# Quad_VCA_no_pots_CTRL_v1.net
KiCad netlist of a schematic drawn in EAGLE
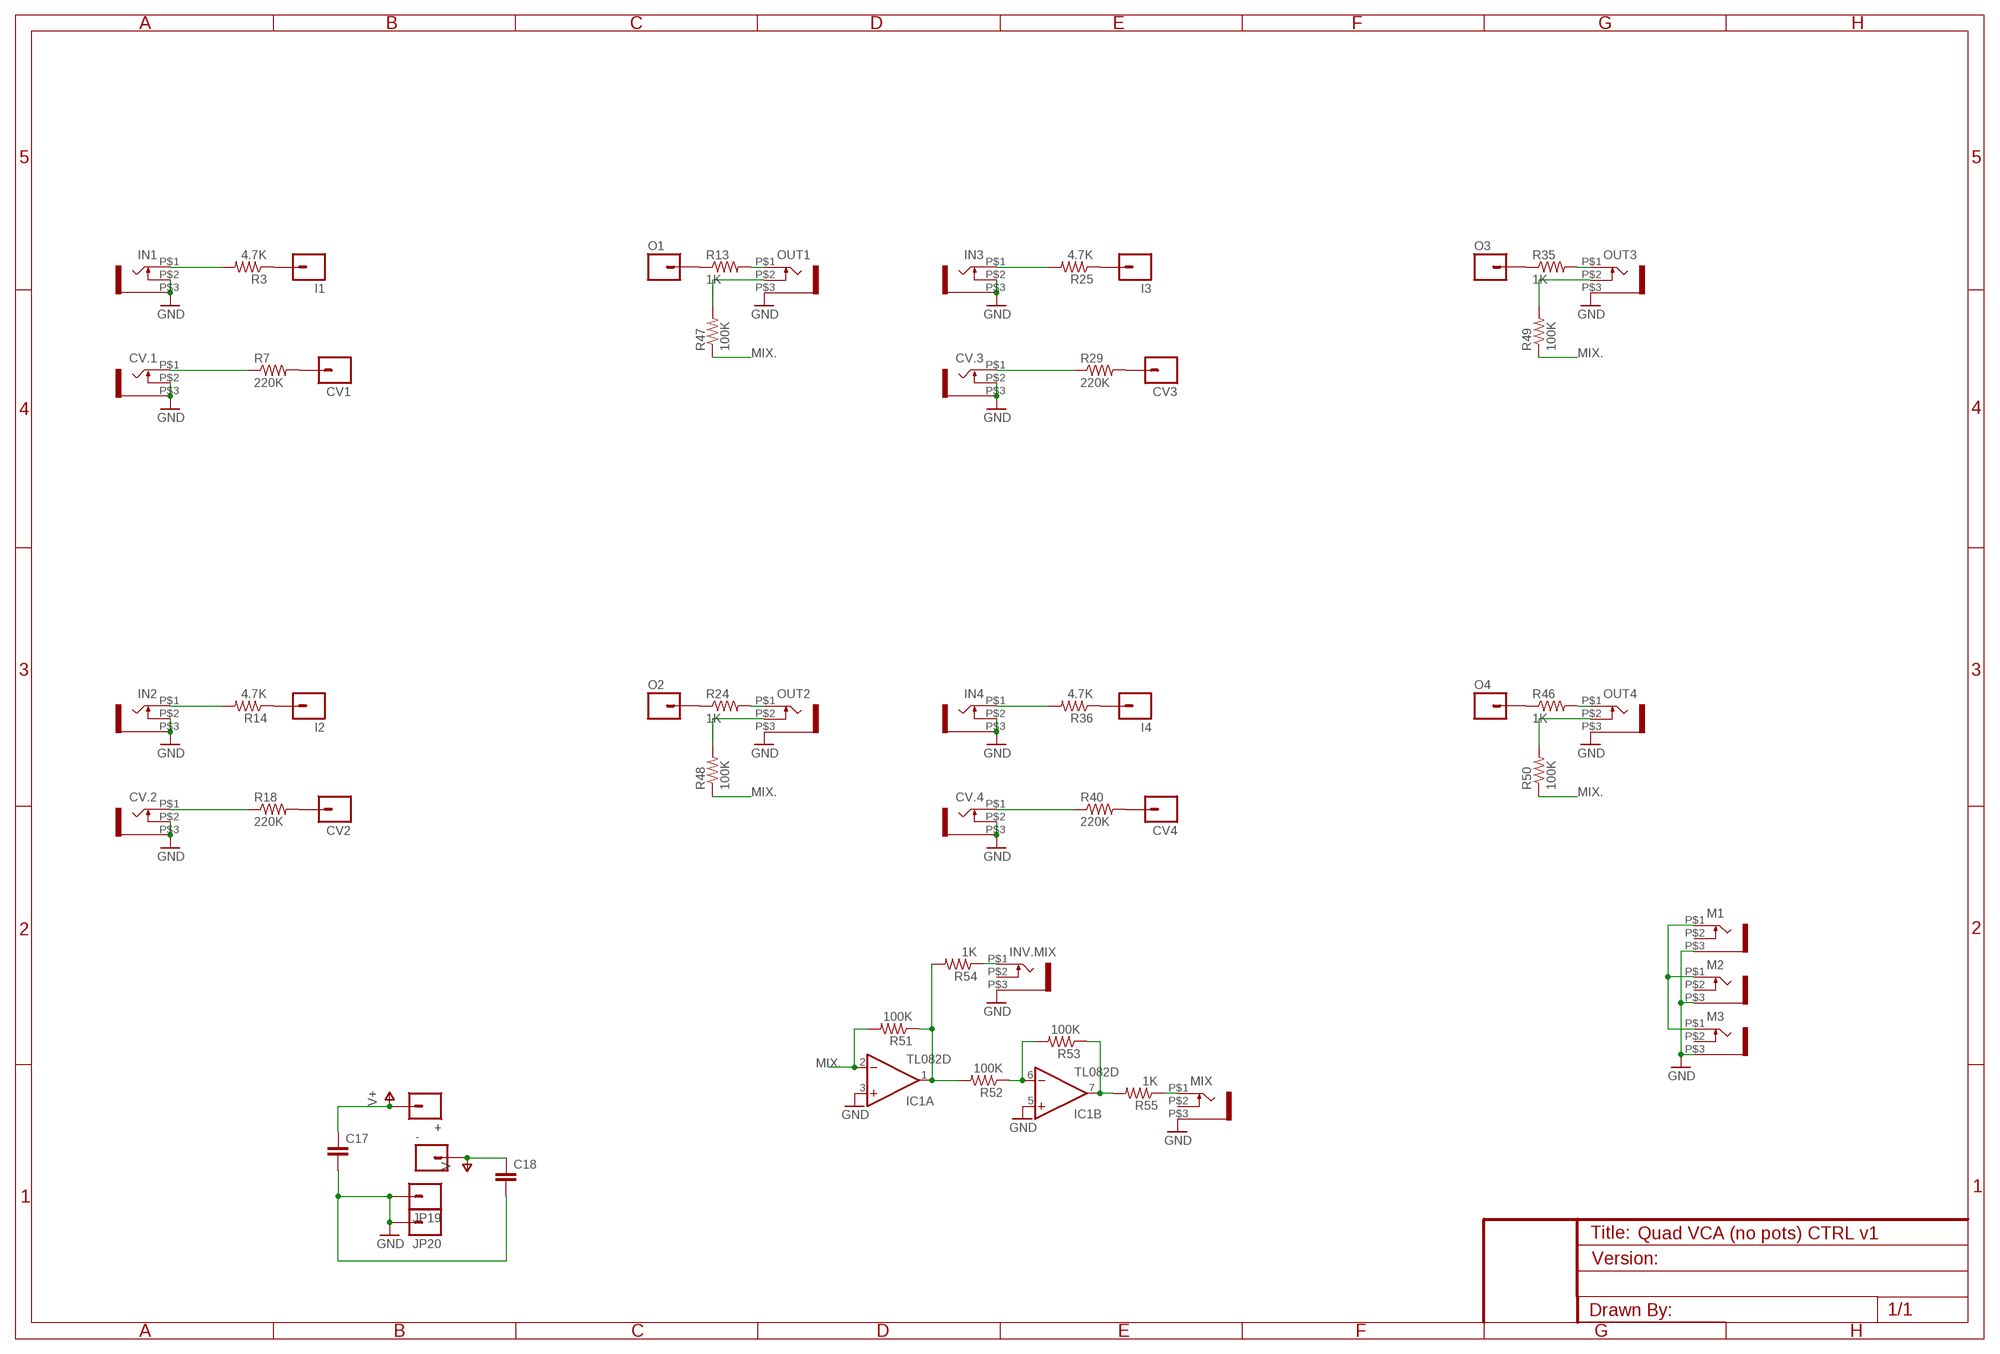
[diagram p0: schematic, sheet 1]

(export (version "E")
  (design (tool "Eeschema 10.0.6"))
  (components
    (comp (ref "+")
      (value "M01PTH")
      (footprint "eagle-import:1X01")
      (libsource (lib "eagle-import") (part "M01PTH"))
    )
    (comp (ref "-")
      (value "M01PTH")
      (footprint "eagle-import:1X01")
      (libsource (lib "eagle-import") (part "M01PTH"))
    )
    (comp (ref "C17")
      (value "CAP0805")
      (footprint "eagle-import:0805")
      (libsource (lib "eagle-import") (part "CAP0805"))
    )
    (comp (ref "C18")
      (value "CAP0805")
      (footprint "eagle-import:0805")
      (libsource (lib "eagle-import") (part "CAP0805"))
    )
    (comp (ref "CV.1")
      (value "WQP-PJ301M-12_JACK")
      (footprint "eagle-import:WQP-PJ301M-12_JACK")
      (libsource (lib "eagle-import") (part "WQP-PJ301M-12_JACK"))
    )
    (comp (ref "CV.2")
      (value "WQP-PJ301M-12_JACK")
      (footprint "eagle-import:WQP-PJ301M-12_JACK")
      (libsource (lib "eagle-import") (part "WQP-PJ301M-12_JACK"))
    )
    (comp (ref "CV.3")
      (value "WQP-PJ301M-12_JACK")
      (footprint "eagle-import:WQP-PJ301M-12_JACK")
      (libsource (lib "eagle-import") (part "WQP-PJ301M-12_JACK"))
    )
    (comp (ref "CV.4")
      (value "WQP-PJ301M-12_JACK")
      (footprint "eagle-import:WQP-PJ301M-12_JACK")
      (libsource (lib "eagle-import") (part "WQP-PJ301M-12_JACK"))
    )
    (comp (ref "CV1")
      (value "M01PTH")
      (footprint "eagle-import:1X01")
      (libsource (lib "eagle-import") (part "M01PTH"))
    )
    (comp (ref "CV2")
      (value "M01PTH")
      (footprint "eagle-import:1X01")
      (libsource (lib "eagle-import") (part "M01PTH"))
    )
    (comp (ref "CV3")
      (value "M01PTH")
      (footprint "eagle-import:1X01")
      (libsource (lib "eagle-import") (part "M01PTH"))
    )
    (comp (ref "CV4")
      (value "M01PTH")
      (footprint "eagle-import:1X01")
      (libsource (lib "eagle-import") (part "M01PTH"))
    )
    (comp (ref "I1")
      (value "M01PTH")
      (footprint "eagle-import:1X01")
      (libsource (lib "eagle-import") (part "M01PTH"))
    )
    (comp (ref "I2")
      (value "M01PTH")
      (footprint "eagle-import:1X01")
      (libsource (lib "eagle-import") (part "M01PTH"))
    )
    (comp (ref "I3")
      (value "M01PTH")
      (footprint "eagle-import:1X01")
      (libsource (lib "eagle-import") (part "M01PTH"))
    )
    (comp (ref "I4")
      (value "M01PTH")
      (footprint "eagle-import:1X01")
      (libsource (lib "eagle-import") (part "M01PTH"))
    )
    (comp (ref "IC1")
      (value "TL082D")
      (footprint "eagle-import:SO08")
      (libsource (lib "eagle-import") (part "TL082D"))
    )
    (comp (ref "IN1")
      (value "WQP-PJ301M-12_JACK")
      (footprint "eagle-import:WQP-PJ301M-12_JACK")
      (libsource (lib "eagle-import") (part "WQP-PJ301M-12_JACK"))
    )
    (comp (ref "IN2")
      (value "WQP-PJ301M-12_JACK")
      (footprint "eagle-import:WQP-PJ301M-12_JACK")
      (libsource (lib "eagle-import") (part "WQP-PJ301M-12_JACK"))
    )
    (comp (ref "IN3")
      (value "WQP-PJ301M-12_JACK")
      (footprint "eagle-import:WQP-PJ301M-12_JACK")
      (libsource (lib "eagle-import") (part "WQP-PJ301M-12_JACK"))
    )
    (comp (ref "IN4")
      (value "WQP-PJ301M-12_JACK")
      (footprint "eagle-import:WQP-PJ301M-12_JACK")
      (libsource (lib "eagle-import") (part "WQP-PJ301M-12_JACK"))
    )
    (comp (ref "INV.MIX")
      (value "WQP-PJ301M-12_JACK")
      (footprint "eagle-import:WQP-PJ301M-12_JACK")
      (libsource (lib "eagle-import") (part "WQP-PJ301M-12_JACK"))
    )
    (comp (ref "JP19")
      (value "M01PTH")
      (footprint "eagle-import:1X01")
      (libsource (lib "eagle-import") (part "M01PTH"))
    )
    (comp (ref "JP20")
      (value "M01PTH")
      (footprint "eagle-import:1X01")
      (libsource (lib "eagle-import") (part "M01PTH"))
    )
    (comp (ref "M1")
      (value "WQP-PJ301M-12_JACK")
      (footprint "eagle-import:WQP-PJ301M-12_JACK")
      (libsource (lib "eagle-import") (part "WQP-PJ301M-12_JACK"))
    )
    (comp (ref "M2")
      (value "WQP-PJ301M-12_JACK")
      (footprint "eagle-import:WQP-PJ301M-12_JACK")
      (libsource (lib "eagle-import") (part "WQP-PJ301M-12_JACK"))
    )
    (comp (ref "M3")
      (value "WQP-PJ301M-12_JACK")
      (footprint "eagle-import:WQP-PJ301M-12_JACK")
      (libsource (lib "eagle-import") (part "WQP-PJ301M-12_JACK"))
    )
    (comp (ref "MIX")
      (value "WQP-PJ301M-12_JACK")
      (footprint "eagle-import:WQP-PJ301M-12_JACK")
      (libsource (lib "eagle-import") (part "WQP-PJ301M-12_JACK"))
    )
    (comp (ref "O1")
      (value "M01PTH")
      (footprint "eagle-import:1X01")
      (libsource (lib "eagle-import") (part "M01PTH"))
    )
    (comp (ref "O2")
      (value "M01PTH")
      (footprint "eagle-import:1X01")
      (libsource (lib "eagle-import") (part "M01PTH"))
    )
    (comp (ref "O3")
      (value "M01PTH")
      (footprint "eagle-import:1X01")
      (libsource (lib "eagle-import") (part "M01PTH"))
    )
    (comp (ref "O4")
      (value "M01PTH")
      (footprint "eagle-import:1X01")
      (libsource (lib "eagle-import") (part "M01PTH"))
    )
    (comp (ref "OUT1")
      (value "WQP-PJ301M-12_JACK")
      (footprint "eagle-import:WQP-PJ301M-12_JACK")
      (libsource (lib "eagle-import") (part "WQP-PJ301M-12_JACK"))
    )
    (comp (ref "OUT2")
      (value "WQP-PJ301M-12_JACK")
      (footprint "eagle-import:WQP-PJ301M-12_JACK")
      (libsource (lib "eagle-import") (part "WQP-PJ301M-12_JACK"))
    )
    (comp (ref "OUT3")
      (value "WQP-PJ301M-12_JACK")
      (footprint "eagle-import:WQP-PJ301M-12_JACK")
      (libsource (lib "eagle-import") (part "WQP-PJ301M-12_JACK"))
    )
    (comp (ref "OUT4")
      (value "WQP-PJ301M-12_JACK")
      (footprint "eagle-import:WQP-PJ301M-12_JACK")
      (libsource (lib "eagle-import") (part "WQP-PJ301M-12_JACK"))
    )
    (comp (ref "R3")
      (value "4.7K")
      (footprint "eagle-import:0805")
      (libsource (lib "eagle-import") (part "RESISTOR0805-RES"))
    )
    (comp (ref "R7")
      (value "220K")
      (footprint "eagle-import:0805")
      (libsource (lib "eagle-import") (part "RESISTOR0805-RES"))
    )
    (comp (ref "R13")
      (value "1K")
      (footprint "eagle-import:0805")
      (libsource (lib "eagle-import") (part "RESISTOR0805-RES"))
    )
    (comp (ref "R14")
      (value "4.7K")
      (footprint "eagle-import:0805")
      (libsource (lib "eagle-import") (part "RESISTOR0805-RES"))
    )
    (comp (ref "R18")
      (value "220K")
      (footprint "eagle-import:0805")
      (libsource (lib "eagle-import") (part "RESISTOR0805-RES"))
    )
    (comp (ref "R24")
      (value "1K")
      (footprint "eagle-import:0805")
      (libsource (lib "eagle-import") (part "RESISTOR0805-RES"))
    )
    (comp (ref "R25")
      (value "4.7K")
      (footprint "eagle-import:0805")
      (libsource (lib "eagle-import") (part "RESISTOR0805-RES"))
    )
    (comp (ref "R29")
      (value "220K")
      (footprint "eagle-import:0805")
      (libsource (lib "eagle-import") (part "RESISTOR0805-RES"))
    )
    (comp (ref "R35")
      (value "1K")
      (footprint "eagle-import:0805")
      (libsource (lib "eagle-import") (part "RESISTOR0805-RES"))
    )
    (comp (ref "R36")
      (value "4.7K")
      (footprint "eagle-import:0805")
      (libsource (lib "eagle-import") (part "RESISTOR0805-RES"))
    )
    (comp (ref "R40")
      (value "220K")
      (footprint "eagle-import:0805")
      (libsource (lib "eagle-import") (part "RESISTOR0805-RES"))
    )
    (comp (ref "R46")
      (value "1K")
      (footprint "eagle-import:0805")
      (libsource (lib "eagle-import") (part "RESISTOR0805-RES"))
    )
    (comp (ref "R47")
      (value "100K")
      (footprint "eagle-import:0805")
      (libsource (lib "eagle-import") (part "RESISTOR0805-RES"))
    )
    (comp (ref "R48")
      (value "100K")
      (footprint "eagle-import:0805")
      (libsource (lib "eagle-import") (part "RESISTOR0805-RES"))
    )
    (comp (ref "R49")
      (value "100K")
      (footprint "eagle-import:0805")
      (libsource (lib "eagle-import") (part "RESISTOR0805-RES"))
    )
    (comp (ref "R50")
      (value "100K")
      (footprint "eagle-import:0805")
      (libsource (lib "eagle-import") (part "RESISTOR0805-RES"))
    )
    (comp (ref "R51")
      (value "100K")
      (footprint "eagle-import:0805")
      (libsource (lib "eagle-import") (part "RESISTOR0805-RES"))
    )
    (comp (ref "R52")
      (value "100K")
      (footprint "eagle-import:0805")
      (libsource (lib "eagle-import") (part "RESISTOR0805-RES"))
    )
    (comp (ref "R53")
      (value "100K")
      (footprint "eagle-import:0805")
      (libsource (lib "eagle-import") (part "RESISTOR0805-RES"))
    )
    (comp (ref "R54")
      (value "1K")
      (footprint "eagle-import:0805")
      (libsource (lib "eagle-import") (part "RESISTOR0805-RES"))
    )
    (comp (ref "R55")
      (value "1K")
      (footprint "eagle-import:0805")
      (libsource (lib "eagle-import") (part "RESISTOR0805-RES"))
    )
  )
  (nets
    (net (code "1") (name "/MIX.") (class "Default")
      (node (ref "IC1") (pin "2") (pinfunction "-IN_2") (pintype "input"))
      (node (ref "R47") (pin "1") (pinfunction "1_1") (pintype "passive"))
      (node (ref "R48") (pin "1") (pinfunction "1_1") (pintype "passive"))
      (node (ref "R49") (pin "1") (pinfunction "1_1") (pintype "passive"))
      (node (ref "R50") (pin "1") (pinfunction "1_1") (pintype "passive"))
      (node (ref "R51") (pin "2") (pinfunction "2_2") (pintype "passive"))
    )
    (net (code "2") (name "GND") (class "Default")
      (node (ref "C17") (pin "2") (pinfunction "2_2") (pintype "passive"))
      (node (ref "C18") (pin "2") (pinfunction "2_2") (pintype "passive"))
      (node (ref "CV.1") (pin "P$2") (pinfunction "3_P$2") (pintype "passive"))
      (node (ref "CV.1") (pin "P$3") (pinfunction "1_P$3") (pintype "passive"))
      (node (ref "CV.2") (pin "P$2") (pinfunction "3_P$2") (pintype "passive"))
      (node (ref "CV.2") (pin "P$3") (pinfunction "1_P$3") (pintype "passive"))
      (node (ref "CV.3") (pin "P$2") (pinfunction "3_P$2") (pintype "passive"))
      (node (ref "CV.3") (pin "P$3") (pinfunction "1_P$3") (pintype "passive"))
      (node (ref "CV.4") (pin "P$2") (pinfunction "3_P$2") (pintype "passive"))
      (node (ref "CV.4") (pin "P$3") (pinfunction "1_P$3") (pintype "passive"))
      (node (ref "IC1") (pin "3") (pinfunction "+IN_3") (pintype "input"))
      (node (ref "IC1") (pin "5") (pinfunction "+IN_5") (pintype "input"))
      (node (ref "IN1") (pin "P$2") (pinfunction "3_P$2") (pintype "passive"))
      (node (ref "IN1") (pin "P$3") (pinfunction "1_P$3") (pintype "passive"))
      (node (ref "IN2") (pin "P$2") (pinfunction "3_P$2") (pintype "passive"))
      (node (ref "IN2") (pin "P$3") (pinfunction "1_P$3") (pintype "passive"))
      (node (ref "IN3") (pin "P$2") (pinfunction "3_P$2") (pintype "passive"))
      (node (ref "IN3") (pin "P$3") (pinfunction "1_P$3") (pintype "passive"))
      (node (ref "IN4") (pin "P$2") (pinfunction "3_P$2") (pintype "passive"))
      (node (ref "IN4") (pin "P$3") (pinfunction "1_P$3") (pintype "passive"))
      (node (ref "INV.MIX") (pin "P$3") (pinfunction "1_P$3") (pintype "passive"))
      (node (ref "JP19") (pin "1") (pinfunction "1_1") (pintype "passive"))
      (node (ref "JP20") (pin "1") (pinfunction "1_1") (pintype "passive"))
      (node (ref "M1") (pin "P$3") (pinfunction "1_P$3") (pintype "passive"))
      (node (ref "M2") (pin "P$3") (pinfunction "1_P$3") (pintype "passive"))
      (node (ref "M3") (pin "P$3") (pinfunction "1_P$3") (pintype "passive"))
      (node (ref "MIX") (pin "P$3") (pinfunction "1_P$3") (pintype "passive"))
      (node (ref "OUT1") (pin "P$3") (pinfunction "1_P$3") (pintype "passive"))
      (node (ref "OUT2") (pin "P$3") (pinfunction "1_P$3") (pintype "passive"))
      (node (ref "OUT3") (pin "P$3") (pinfunction "1_P$3") (pintype "passive"))
      (node (ref "OUT4") (pin "P$3") (pinfunction "1_P$3") (pintype "passive"))
    )
    (net (code "3") (name "Net-(CV.1-2)") (class "Default")
      (node (ref "CV.1") (pin "P$1") (pinfunction "2_P$1") (pintype "passive"))
      (node (ref "R7") (pin "1") (pinfunction "1_1") (pintype "passive"))
    )
    (net (code "4") (name "Net-(CV.2-2)") (class "Default")
      (node (ref "CV.2") (pin "P$1") (pinfunction "2_P$1") (pintype "passive"))
      (node (ref "R18") (pin "1") (pinfunction "1_1") (pintype "passive"))
    )
    (net (code "5") (name "Net-(CV.3-2)") (class "Default")
      (node (ref "CV.3") (pin "P$1") (pinfunction "2_P$1") (pintype "passive"))
      (node (ref "R29") (pin "1") (pinfunction "1_1") (pintype "passive"))
    )
    (net (code "6") (name "Net-(CV.4-2)") (class "Default")
      (node (ref "CV.4") (pin "P$1") (pinfunction "2_P$1") (pintype "passive"))
      (node (ref "R40") (pin "1") (pinfunction "1_1") (pintype "passive"))
    )
    (net (code "7") (name "Net-(CV1-Pad1)") (class "Default")
      (node (ref "CV1") (pin "1") (pinfunction "1_1") (pintype "passive"))
      (node (ref "R7") (pin "2") (pinfunction "2_2") (pintype "passive"))
    )
    (net (code "8") (name "Net-(CV2-Pad1)") (class "Default")
      (node (ref "CV2") (pin "1") (pinfunction "1_1") (pintype "passive"))
      (node (ref "R18") (pin "2") (pinfunction "2_2") (pintype "passive"))
    )
    (net (code "9") (name "Net-(CV3-Pad1)") (class "Default")
      (node (ref "CV3") (pin "1") (pinfunction "1_1") (pintype "passive"))
      (node (ref "R29") (pin "2") (pinfunction "2_2") (pintype "passive"))
    )
    (net (code "10") (name "Net-(CV4-Pad1)") (class "Default")
      (node (ref "CV4") (pin "1") (pinfunction "1_1") (pintype "passive"))
      (node (ref "R40") (pin "2") (pinfunction "2_2") (pintype "passive"))
    )
    (net (code "11") (name "Net-(I1-Pad1)") (class "Default")
      (node (ref "I1") (pin "1") (pinfunction "1_1") (pintype "passive"))
      (node (ref "R3") (pin "1") (pinfunction "1_1") (pintype "passive"))
    )
    (net (code "12") (name "Net-(I2-Pad1)") (class "Default")
      (node (ref "I2") (pin "1") (pinfunction "1_1") (pintype "passive"))
      (node (ref "R14") (pin "1") (pinfunction "1_1") (pintype "passive"))
    )
    (net (code "13") (name "Net-(I3-Pad1)") (class "Default")
      (node (ref "I3") (pin "1") (pinfunction "1_1") (pintype "passive"))
      (node (ref "R25") (pin "1") (pinfunction "1_1") (pintype "passive"))
    )
    (net (code "14") (name "Net-(I4-Pad1)") (class "Default")
      (node (ref "I4") (pin "1") (pinfunction "1_1") (pintype "passive"))
      (node (ref "R36") (pin "1") (pinfunction "1_1") (pintype "passive"))
    )
    (net (code "15") (name "Net-(IC1A-OUT)") (class "Default")
      (node (ref "IC1") (pin "1") (pinfunction "OUT_1") (pintype "output"))
      (node (ref "R51") (pin "1") (pinfunction "1_1") (pintype "passive"))
      (node (ref "R52") (pin "2") (pinfunction "2_2") (pintype "passive"))
      (node (ref "R54") (pin "2") (pinfunction "2_2") (pintype "passive"))
    )
    (net (code "16") (name "Net-(IC1B--IN)") (class "Default")
      (node (ref "IC1") (pin "6") (pinfunction "-IN_6") (pintype "input"))
      (node (ref "R52") (pin "1") (pinfunction "1_1") (pintype "passive"))
      (node (ref "R53") (pin "2") (pinfunction "2_2") (pintype "passive"))
    )
    (net (code "17") (name "Net-(IC1B-OUT)") (class "Default")
      (node (ref "IC1") (pin "7") (pinfunction "OUT_7") (pintype "output"))
      (node (ref "R53") (pin "1") (pinfunction "1_1") (pintype "passive"))
      (node (ref "R55") (pin "2") (pinfunction "2_2") (pintype "passive"))
    )
    (net (code "18") (name "Net-(IN1-2)") (class "Default")
      (node (ref "IN1") (pin "P$1") (pinfunction "2_P$1") (pintype "passive"))
      (node (ref "R3") (pin "2") (pinfunction "2_2") (pintype "passive"))
    )
    (net (code "19") (name "Net-(IN2-2)") (class "Default")
      (node (ref "IN2") (pin "P$1") (pinfunction "2_P$1") (pintype "passive"))
      (node (ref "R14") (pin "2") (pinfunction "2_2") (pintype "passive"))
    )
    (net (code "20") (name "Net-(IN3-2)") (class "Default")
      (node (ref "IN3") (pin "P$1") (pinfunction "2_P$1") (pintype "passive"))
      (node (ref "R25") (pin "2") (pinfunction "2_2") (pintype "passive"))
    )
    (net (code "21") (name "Net-(IN4-2)") (class "Default")
      (node (ref "IN4") (pin "P$1") (pinfunction "2_P$1") (pintype "passive"))
      (node (ref "R36") (pin "2") (pinfunction "2_2") (pintype "passive"))
    )
    (net (code "22") (name "Net-(INV.MIX-2)") (class "Default")
      (node (ref "INV.MIX") (pin "P$1") (pinfunction "2_P$1") (pintype "passive"))
      (node (ref "R54") (pin "1") (pinfunction "1_1") (pintype "passive"))
    )
    (net (code "23") (name "Net-(M1-2)") (class "Default")
      (node (ref "M1") (pin "P$1") (pinfunction "2_P$1") (pintype "passive"))
      (node (ref "M2") (pin "P$1") (pinfunction "2_P$1") (pintype "passive"))
      (node (ref "M3") (pin "P$1") (pinfunction "2_P$1") (pintype "passive"))
    )
    (net (code "24") (name "Net-(MIX-2)") (class "Default")
      (node (ref "MIX") (pin "P$1") (pinfunction "2_P$1") (pintype "passive"))
      (node (ref "R55") (pin "1") (pinfunction "1_1") (pintype "passive"))
    )
    (net (code "25") (name "Net-(O1-Pad1)") (class "Default")
      (node (ref "O1") (pin "1") (pinfunction "1_1") (pintype "passive"))
      (node (ref "R13") (pin "1") (pinfunction "1_1") (pintype "passive"))
    )
    (net (code "26") (name "Net-(O2-Pad1)") (class "Default")
      (node (ref "O2") (pin "1") (pinfunction "1_1") (pintype "passive"))
      (node (ref "R24") (pin "1") (pinfunction "1_1") (pintype "passive"))
    )
    (net (code "27") (name "Net-(O3-Pad1)") (class "Default")
      (node (ref "O3") (pin "1") (pinfunction "1_1") (pintype "passive"))
      (node (ref "R35") (pin "1") (pinfunction "1_1") (pintype "passive"))
    )
    (net (code "28") (name "Net-(O4-Pad1)") (class "Default")
      (node (ref "O4") (pin "1") (pinfunction "1_1") (pintype "passive"))
      (node (ref "R46") (pin "1") (pinfunction "1_1") (pintype "passive"))
    )
    (net (code "29") (name "Net-(OUT1-2)") (class "Default")
      (node (ref "OUT1") (pin "P$1") (pinfunction "2_P$1") (pintype "passive"))
      (node (ref "R13") (pin "2") (pinfunction "2_2") (pintype "passive"))
    )
    (net (code "30") (name "Net-(OUT1-3)") (class "Default")
      (node (ref "OUT1") (pin "P$2") (pinfunction "3_P$2") (pintype "passive"))
      (node (ref "R47") (pin "2") (pinfunction "2_2") (pintype "passive"))
    )
    (net (code "31") (name "Net-(OUT2-2)") (class "Default")
      (node (ref "OUT2") (pin "P$1") (pinfunction "2_P$1") (pintype "passive"))
      (node (ref "R24") (pin "2") (pinfunction "2_2") (pintype "passive"))
    )
    (net (code "32") (name "Net-(OUT2-3)") (class "Default")
      (node (ref "OUT2") (pin "P$2") (pinfunction "3_P$2") (pintype "passive"))
      (node (ref "R48") (pin "2") (pinfunction "2_2") (pintype "passive"))
    )
    (net (code "33") (name "Net-(OUT3-2)") (class "Default")
      (node (ref "OUT3") (pin "P$1") (pinfunction "2_P$1") (pintype "passive"))
      (node (ref "R35") (pin "2") (pinfunction "2_2") (pintype "passive"))
    )
    (net (code "34") (name "Net-(OUT3-3)") (class "Default")
      (node (ref "OUT3") (pin "P$2") (pinfunction "3_P$2") (pintype "passive"))
      (node (ref "R49") (pin "2") (pinfunction "2_2") (pintype "passive"))
    )
    (net (code "35") (name "Net-(OUT4-2)") (class "Default")
      (node (ref "OUT4") (pin "P$1") (pinfunction "2_P$1") (pintype "passive"))
      (node (ref "R46") (pin "2") (pinfunction "2_2") (pintype "passive"))
    )
    (net (code "36") (name "Net-(OUT4-3)") (class "Default")
      (node (ref "OUT4") (pin "P$2") (pinfunction "3_P$2") (pintype "passive"))
      (node (ref "R50") (pin "2") (pinfunction "2_2") (pintype "passive"))
    )
    (net (code "37") (name "V+") (class "Default")
      (node (ref "+") (pin "1") (pinfunction "1_1") (pintype "passive"))
      (node (ref "C17") (pin "1") (pinfunction "1_1") (pintype "passive"))
    )
    (net (code "38") (name "V-") (class "Default")
      (node (ref "-") (pin "1") (pinfunction "1_1") (pintype "passive"))
      (node (ref "C18") (pin "1") (pinfunction "1_1") (pintype "passive"))
    )
    (net (code "39") (name "unconnected-(INV.MIX-3-PadP$2)") (class "Default")
      (node (ref "INV.MIX") (pin "P$2") (pinfunction "3_P$2") (pintype "passive"))
    )
    (net (code "40") (name "unconnected-(M1-3-PadP$2)") (class "Default")
      (node (ref "M1") (pin "P$2") (pinfunction "3_P$2") (pintype "passive"))
    )
    (net (code "41") (name "unconnected-(M2-3-PadP$2)") (class "Default")
      (node (ref "M2") (pin "P$2") (pinfunction "3_P$2") (pintype "passive"))
    )
    (net (code "42") (name "unconnected-(M3-3-PadP$2)") (class "Default")
      (node (ref "M3") (pin "P$2") (pinfunction "3_P$2") (pintype "passive"))
    )
    (net (code "43") (name "unconnected-(MIX-3-PadP$2)") (class "Default")
      (node (ref "MIX") (pin "P$2") (pinfunction "3_P$2") (pintype "passive"))
    )
  )
)
